# High_Side_FETs.net
KiCad netlist of a schematic drawn in Altium Designer
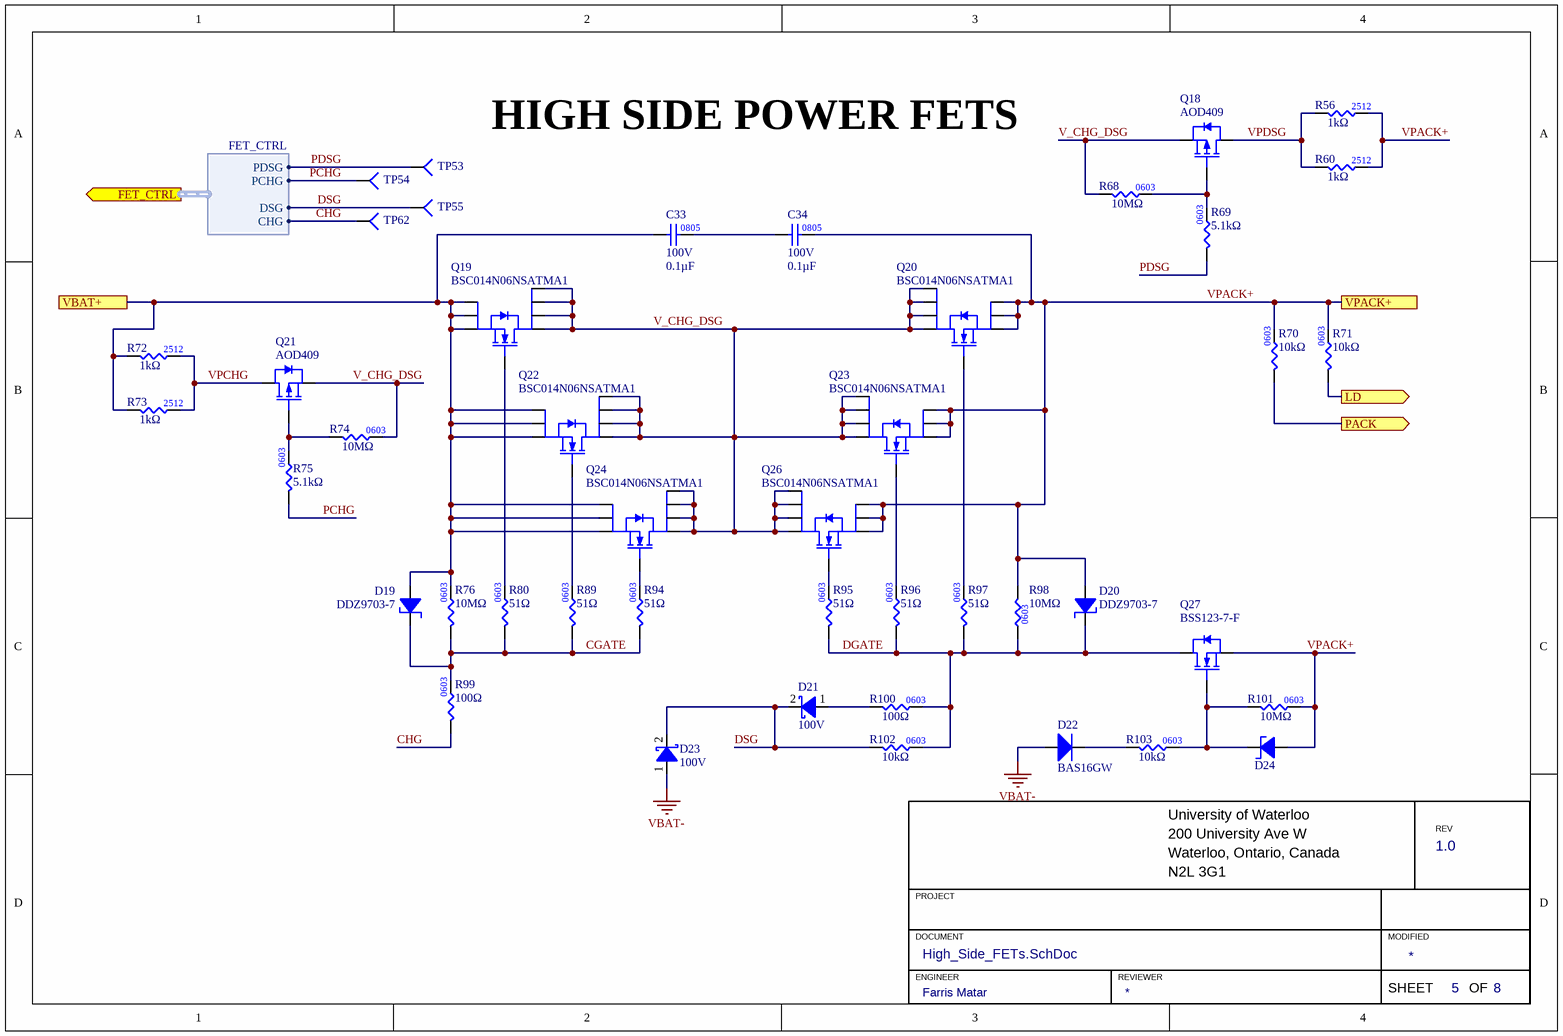
[diagram p0: High_Side_FETs.SchDoc]

(export (version "E")
  (design (tool "Eeschema 10.0.6"))
  (components
    (comp (ref "C33")
      (value "0.1µF")
      (footprint "CAP0805")
      (description "CAP CER 0.1UF 100V X7R 0805")
      (fields (field (name "VOLTAGE RATING") "100V") (field (name "Comment") "CAP_0.1uF_100V_0805"))
      (libsource (lib "Personal_Schematic_Library_2022") (part "CAP_0.1uF_100V_0805"))
    )
    (comp (ref "C34")
      (value "0.1µF")
      (footprint "CAP0805")
      (description "CAP CER 0.1UF 100V X7R 0805")
      (fields (field (name "VOLTAGE RATING") "100V") (field (name "Comment") "CAP_0.1uF_100V_0805"))
      (libsource (lib "Personal_Schematic_Library_2022") (part "CAP_0.1uF_100V_0805"))
    )
    (comp (ref "D19")
      (value "DIO_ZENER_16V")
      (footprint "SOD-123_FLAT")
      (description "DIODE ZENER 16V 500MW SOD123")
      (fields (field (name "MANUFACTURER PART NUMBER 1") "DDZ9703-7"))
      (libsource (lib "Personal_Schematic_Library_2022") (part "DIO_ZENER_16V"))
    )
    (comp (ref "D20")
      (value "DIO_ZENER_16V")
      (footprint "SOD-123_FLAT")
      (description "DIODE ZENER 16V 500MW SOD123")
      (fields (field (name "MANUFACTURER PART NUMBER 1") "DDZ9703-7"))
      (libsource (lib "Personal_Schematic_Library_2022") (part "DIO_ZENER_16V"))
    )
    (comp (ref "D21")
      (value "DIO_SCHOTTKY_100V_1A")
      (footprint "SOD-123_FLAT")
      (description "DIODE SCHOTTKY 100V 1A SOD-123F")
      (fields (field (name "VR (MAX)") "100V"))
      (libsource (lib "Personal_Schematic_Library_2022") (part "DIO_SCHOTTKY_100V_1A"))
    )
    (comp (ref "D22")
      (value "DIO_100V_215mA")
      (footprint "DIODSOD-123")
      (description "DIODE GEN PURP 100V 215MA SOD123")
      (fields (field (name "MANUFACTURER PART NUMBER 1") "BAS16GW"))
      (libsource (lib "Personal_Schematic_Library_2022") (part "DIO_100V_215mA"))
    )
    (comp (ref "D23")
      (value "DIO_SCHOTTKY_100V_1A")
      (footprint "SOD-123_FLAT")
      (description "DIODE SCHOTTKY 100V 1A SOD-123F")
      (fields (field (name "VR (MAX)") "100V"))
      (libsource (lib "Personal_Schematic_Library_2022") (part "DIO_SCHOTTKY_100V_1A"))
    )
    (comp (ref "D24")
      (value "DIO_ZENER_16V")
      (footprint "SOD-123_FLAT")
      (description "DIODE ZENER 16V 500MW SOD123")
      (libsource (lib "Personal_Schematic_Library_2022") (part "DIO_ZENER_16V"))
    )
    (comp (ref "Q18")
      (value "PMOS_60V_26A")
      (footprint "TO-252 AOSMD")
      (description "MOSFET P-CH 60V 26A TO252")
      (fields (field (name "MANUFACTURER PART NUMBER 1") "AOD409"))
      (libsource (lib "Personal_Schematic_Library_2022") (part "PMOS_60V_26A"))
    )
    (comp (ref "Q19")
      (value "NMOS_60V_30A")
      (footprint "INFINEON_8-POWERTDFN")
      (description "MOSFET N-CH 60V 30A/100A TDSON7")
      (fields (field (name "MANUFACTURER PART NUMBER 1") "BSC014N06NSATMA1"))
      (libsource (lib "Personal_Schematic_Library_2022") (part "NMOS_60V_30A"))
    )
    (comp (ref "Q20")
      (value "NMOS_60V_30A")
      (footprint "INFINEON_8-POWERTDFN")
      (description "MOSFET N-CH 60V 30A/100A TDSON7")
      (fields (field (name "MANUFACTURER PART NUMBER 1") "BSC014N06NSATMA1"))
      (libsource (lib "Personal_Schematic_Library_2022") (part "NMOS_60V_30A"))
    )
    (comp (ref "Q21")
      (value "PMOS_60V_26A")
      (footprint "TO-252 AOSMD")
      (description "MOSFET P-CH 60V 26A TO252")
      (fields (field (name "MANUFACTURER PART NUMBER 1") "AOD409"))
      (libsource (lib "Personal_Schematic_Library_2022") (part "PMOS_60V_26A"))
    )
    (comp (ref "Q22")
      (value "NMOS_60V_30A")
      (footprint "INFINEON_8-POWERTDFN")
      (description "MOSFET N-CH 60V 30A/100A TDSON7")
      (fields (field (name "MANUFACTURER PART NUMBER 1") "BSC014N06NSATMA1"))
      (libsource (lib "Personal_Schematic_Library_2022") (part "NMOS_60V_30A"))
    )
    (comp (ref "Q23")
      (value "NMOS_60V_30A")
      (footprint "INFINEON_8-POWERTDFN")
      (description "MOSFET N-CH 60V 30A/100A TDSON7")
      (fields (field (name "MANUFACTURER PART NUMBER 1") "BSC014N06NSATMA1"))
      (libsource (lib "Personal_Schematic_Library_2022") (part "NMOS_60V_30A"))
    )
    (comp (ref "Q24")
      (value "NMOS_60V_30A")
      (footprint "INFINEON_8-POWERTDFN")
      (description "MOSFET N-CH 60V 30A/100A TDSON7")
      (fields (field (name "MANUFACTURER PART NUMBER 1") "BSC014N06NSATMA1"))
      (libsource (lib "Personal_Schematic_Library_2022") (part "NMOS_60V_30A"))
    )
    (comp (ref "Q26")
      (value "NMOS_60V_30A")
      (footprint "INFINEON_8-POWERTDFN")
      (description "MOSFET N-CH 60V 30A/100A TDSON7")
      (fields (field (name "MANUFACTURER PART NUMBER 1") "BSC014N06NSATMA1"))
      (libsource (lib "Personal_Schematic_Library_2022") (part "NMOS_60V_30A"))
    )
    (comp (ref "Q27")
      (value "NMOS_100V_170mA")
      (footprint "SOT23-3")
      (description "MOSFET N-CH 100V 170MA SOT23-3")
      (fields (field (name "MANUFACTURER PART NUMBER 1") "BSS123-7-F"))
      (libsource (lib "Personal_Schematic_Library_2022") (part "NMOS_100V_170mA"))
    )
    (comp (ref "R56")
      (value "1kΩ")
      (footprint "RES2512")
      (description "RES SMD 1K OHM 1% 3W 2512")
      (fields (field (name "Comment") "RES_1kΩ_2512_1%"))
      (libsource (lib "Personal_Schematic_Library_2022") (part "RES_1kΩ_2512_1%"))
    )
    (comp (ref "R60")
      (value "1kΩ")
      (footprint "RES2512")
      (description "RES SMD 1K OHM 1% 3W 2512")
      (fields (field (name "Comment") "RES_1kΩ_2512_1%"))
      (libsource (lib "Personal_Schematic_Library_2022") (part "RES_1kΩ_2512_1%"))
    )
    (comp (ref "R68")
      (value "10MΩ")
      (footprint "RES0603")
      (description "RES 10M OHM 1% 1/10W 0603")
      (fields (field (name "Comment") "RES_10MΩ_0603_1%"))
      (libsource (lib "Personal_Schematic_Library_2022") (part "RES_10MΩ_0603_1%"))
    )
    (comp (ref "R69")
      (value "5.1kΩ")
      (footprint "RES0603")
      (description "RES 5.1K OHM 1% 1/10W 0603")
      (fields (field (name "Comment") "RES_5.1kΩ_0603_1%"))
      (libsource (lib "Personal_Schematic_Library_2022") (part "RES_5.1kΩ_0603_1%"))
    )
    (comp (ref "R70")
      (value "10kΩ")
      (footprint "RES0603")
      (description "RES 10K OHM 1% 1/8W 0603")
      (fields (field (name "Comment") "RES_10kΩ_0603_1%"))
      (libsource (lib "Personal_Schematic_Library_2022") (part "RES_10kΩ_0603_1%"))
    )
    (comp (ref "R71")
      (value "10kΩ")
      (footprint "RES0603")
      (description "RES 10K OHM 1% 1/8W 0603")
      (fields (field (name "Comment") "RES_10kΩ_0603_1%"))
      (libsource (lib "Personal_Schematic_Library_2022") (part "RES_10kΩ_0603_1%"))
    )
    (comp (ref "R72")
      (value "1kΩ")
      (footprint "RES2512")
      (description "RES SMD 1K OHM 1% 3W 2512")
      (fields (field (name "Comment") "RES_1kΩ_2512_1%"))
      (libsource (lib "Personal_Schematic_Library_2022") (part "RES_1kΩ_2512_1%"))
    )
    (comp (ref "R73")
      (value "1kΩ")
      (footprint "RES2512")
      (description "RES SMD 1K OHM 1% 3W 2512")
      (fields (field (name "Comment") "RES_1kΩ_2512_1%"))
      (libsource (lib "Personal_Schematic_Library_2022") (part "RES_1kΩ_2512_1%"))
    )
    (comp (ref "R74")
      (value "10MΩ")
      (footprint "RES0603")
      (description "RES 10M OHM 1% 1/10W 0603")
      (fields (field (name "Comment") "RES_10MΩ_0603_1%"))
      (libsource (lib "Personal_Schematic_Library_2022") (part "RES_10MΩ_0603_1%"))
    )
    (comp (ref "R75")
      (value "5.1kΩ")
      (footprint "RES0603")
      (description "RES 5.1K OHM 1% 1/10W 0603")
      (fields (field (name "Comment") "RES_5.1kΩ_0603_1%"))
      (libsource (lib "Personal_Schematic_Library_2022") (part "RES_5.1kΩ_0603_1%"))
    )
    (comp (ref "R76")
      (value "10MΩ")
      (footprint "RES0603")
      (description "RES 10M OHM 1% 1/10W 0603")
      (fields (field (name "Comment") "RES_10MΩ_0603_1%"))
      (libsource (lib "Personal_Schematic_Library_2022") (part "RES_10MΩ_0603_1%"))
    )
    (comp (ref "R80")
      (value "51Ω")
      (footprint "RES0603")
      (description "RES 51 OHM 1% 1/10W 0603")
      (fields (field (name "Comment") "RES_51Ω_0603_1%"))
      (libsource (lib "Personal_Schematic_Library_2022") (part "RES_51Ω_0603_1%"))
    )
    (comp (ref "R89")
      (value "51Ω")
      (footprint "RES0603")
      (description "RES 51 OHM 1% 1/10W 0603")
      (fields (field (name "Comment") "RES_51Ω_0603_1%"))
      (libsource (lib "Personal_Schematic_Library_2022") (part "RES_51Ω_0603_1%"))
    )
    (comp (ref "R94")
      (value "51Ω")
      (footprint "RES0603")
      (description "RES 51 OHM 1% 1/10W 0603")
      (fields (field (name "Comment") "RES_51Ω_0603_1%"))
      (libsource (lib "Personal_Schematic_Library_2022") (part "RES_51Ω_0603_1%"))
    )
    (comp (ref "R95")
      (value "51Ω")
      (footprint "RES0603")
      (description "RES 51 OHM 1% 1/10W 0603")
      (fields (field (name "Comment") "RES_51Ω_0603_1%"))
      (libsource (lib "Personal_Schematic_Library_2022") (part "RES_51Ω_0603_1%"))
    )
    (comp (ref "R96")
      (value "51Ω")
      (footprint "RES0603")
      (description "RES 51 OHM 1% 1/10W 0603")
      (fields (field (name "Comment") "RES_51Ω_0603_1%"))
      (libsource (lib "Personal_Schematic_Library_2022") (part "RES_51Ω_0603_1%"))
    )
    (comp (ref "R97")
      (value "51Ω")
      (footprint "RES0603")
      (description "RES 51 OHM 1% 1/10W 0603")
      (fields (field (name "Comment") "RES_51Ω_0603_1%"))
      (libsource (lib "Personal_Schematic_Library_2022") (part "RES_51Ω_0603_1%"))
    )
    (comp (ref "R98")
      (value "10MΩ")
      (footprint "RES0603")
      (description "RES 10M OHM 1% 1/10W 0603")
      (fields (field (name "Comment") "RES_10MΩ_0603_1%"))
      (libsource (lib "Personal_Schematic_Library_2022") (part "RES_10MΩ_0603_1%"))
    )
    (comp (ref "R99")
      (value "100Ω")
      (footprint "RES0603")
      (description "RES 100 OHM 1% 1/10W 0603")
      (fields (field (name "Comment") "RES_100Ω_0603_1%"))
      (libsource (lib "Personal_Schematic_Library_2022") (part "RES_100Ω_0603_1%"))
    )
    (comp (ref "R100")
      (value "100Ω")
      (footprint "RES0603")
      (description "RES 100 OHM 1% 1/10W 0603")
      (fields (field (name "Comment") "RES_100Ω_0603_1%"))
      (libsource (lib "Personal_Schematic_Library_2022") (part "RES_100Ω_0603_1%"))
    )
    (comp (ref "R101")
      (value "10MΩ")
      (footprint "RES0603")
      (description "RES 10M OHM 1% 1/10W 0603")
      (fields (field (name "Comment") "RES_10MΩ_0603_1%"))
      (libsource (lib "Personal_Schematic_Library_2022") (part "RES_10MΩ_0603_1%"))
    )
    (comp (ref "R102")
      (value "10kΩ")
      (footprint "RES0603")
      (description "RES 10K OHM 1% 1/8W 0603")
      (fields (field (name "Comment") "RES_10kΩ_0603_1%"))
      (libsource (lib "Personal_Schematic_Library_2022") (part "RES_10kΩ_0603_1%"))
    )
    (comp (ref "R103")
      (value "10kΩ")
      (footprint "RES0603")
      (description "RES 10K OHM 1% 1/8W 0603")
      (fields (field (name "Comment") "RES_10kΩ_0603_1%"))
      (libsource (lib "Personal_Schematic_Library_2022") (part "RES_10kΩ_0603_1%"))
    )
    (comp (ref "TP53")
      (value "TESTPOINT_1MM_CIRCLE")
      (footprint "TESTPOINT_CIRCLE_1MM")
      (description "TESTPOINT 1MM CIRCLE")
      (libsource (lib "Personal_Schematic_Library_2022") (part "TESTPOINT_1MM_CIRCLE"))
    )
    (comp (ref "TP54")
      (value "TESTPOINT_1MM_CIRCLE")
      (footprint "TESTPOINT_CIRCLE_1MM")
      (description "TESTPOINT 1MM CIRCLE")
      (libsource (lib "Personal_Schematic_Library_2022") (part "TESTPOINT_1MM_CIRCLE"))
    )
    (comp (ref "TP55")
      (value "TESTPOINT_1MM_CIRCLE")
      (footprint "TESTPOINT_CIRCLE_1MM")
      (description "TESTPOINT 1MM CIRCLE")
      (libsource (lib "Personal_Schematic_Library_2022") (part "TESTPOINT_1MM_CIRCLE"))
    )
    (comp (ref "TP62")
      (value "TESTPOINT_1MM_CIRCLE")
      (footprint "TESTPOINT_CIRCLE_1MM")
      (description "TESTPOINT 1MM CIRCLE")
      (libsource (lib "Personal_Schematic_Library_2022") (part "TESTPOINT_1MM_CIRCLE"))
    )
  )
  (nets
    (net (code "2") (name "/CGATE") (class "Default")
      (node (ref "D19") (pin "2") (pinfunction "Cathode_2") (pintype "passive"))
      (node (ref "R76") (pin "1") (pinfunction "1_1") (pintype "passive"))
      (node (ref "R80") (pin "1") (pinfunction "1_1") (pintype "passive"))
      (node (ref "R89") (pin "1") (pinfunction "1_1") (pintype "passive"))
      (node (ref "R94") (pin "1") (pinfunction "1_1") (pintype "passive"))
      (node (ref "R99") (pin "2") (pinfunction "2_2") (pintype "passive"))
    )
    (net (code "3") (name "/CHG") (class "Default")
      (node (ref "R99") (pin "1") (pinfunction "1_1") (pintype "passive"))
      (node (ref "TP62") (pin "1") (pinfunction "=value_1") (pintype "passive"))
    )
    (net (code "4") (name "/DGATE") (class "Default")
      (node (ref "D20") (pin "2") (pinfunction "Cathode_2") (pintype "passive"))
      (node (ref "Q27") (pin "3") (pinfunction "DRAIN_3") (pintype "passive"))
      (node (ref "R100") (pin "2") (pinfunction "2_2") (pintype "passive"))
      (node (ref "R102") (pin "2") (pinfunction "2_2") (pintype "passive"))
      (node (ref "R95") (pin "1") (pinfunction "1_1") (pintype "passive"))
      (node (ref "R96") (pin "1") (pinfunction "1_1") (pintype "passive"))
      (node (ref "R97") (pin "1") (pinfunction "1_1") (pintype "passive"))
      (node (ref "R98") (pin "1") (pinfunction "1_1") (pintype "passive"))
    )
    (net (code "5") (name "/DSG") (class "Default")
      (node (ref "D21") (pin "2") (pinfunction "Cathode_2") (pintype "passive"))
      (node (ref "D23") (pin "2") (pinfunction "Cathode_2") (pintype "passive"))
      (node (ref "R102") (pin "1") (pinfunction "1_1") (pintype "passive"))
      (node (ref "TP55") (pin "1") (pinfunction "=value_1") (pintype "passive"))
    )
    (net (code "6") (name "/LD") (class "Default")
      (node (ref "R71") (pin "1") (pinfunction "1_1") (pintype "passive"))
    )
    (net (code "7") (name "/PACK") (class "Default")
      (node (ref "R70") (pin "1") (pinfunction "1_1") (pintype "passive"))
    )
    (net (code "8") (name "/PCHG") (class "Default")
      (node (ref "R75") (pin "1") (pinfunction "1_1") (pintype "passive"))
      (node (ref "TP54") (pin "1") (pinfunction "=value_1") (pintype "passive"))
    )
    (net (code "9") (name "/PDSG") (class "Default")
      (node (ref "R69") (pin "1") (pinfunction "1_1") (pintype "passive"))
      (node (ref "TP53") (pin "1") (pinfunction "=value_1") (pintype "passive"))
    )
    (net (code "10") (name "/VBAT+") (class "Default")
      (node (ref "C33") (pin "1") (pinfunction "1_1") (pintype "passive"))
      (node (ref "D19") (pin "1") (pinfunction "Anode_1") (pintype "passive"))
      (node (ref "Q19") (pin "1") (pinfunction "Source_1") (pintype "passive"))
      (node (ref "Q19") (pin "2") (pinfunction "Source_2") (pintype "passive"))
      (node (ref "Q19") (pin "3") (pinfunction "Source_3") (pintype "passive"))
      (node (ref "Q22") (pin "1") (pinfunction "Source_1") (pintype "passive"))
      (node (ref "Q22") (pin "2") (pinfunction "Source_2") (pintype "passive"))
      (node (ref "Q22") (pin "3") (pinfunction "Source_3") (pintype "passive"))
      (node (ref "Q24") (pin "1") (pinfunction "Source_1") (pintype "passive"))
      (node (ref "Q24") (pin "2") (pinfunction "Source_2") (pintype "passive"))
      (node (ref "Q24") (pin "3") (pinfunction "Source_3") (pintype "passive"))
      (node (ref "R72") (pin "1") (pinfunction "1_1") (pintype "passive"))
      (node (ref "R73") (pin "1") (pinfunction "1_1") (pintype "passive"))
      (node (ref "R76") (pin "2") (pinfunction "2_2") (pintype "passive"))
    )
    (net (code "11") (name "/VPACK+") (class "Default")
      (node (ref "C34") (pin "2") (pinfunction "2_2") (pintype "passive"))
      (node (ref "D20") (pin "1") (pinfunction "Anode_1") (pintype "passive"))
      (node (ref "D24") (pin "1") (pinfunction "Anode_1") (pintype "passive"))
      (node (ref "Q20") (pin "1") (pinfunction "Source_1") (pintype "passive"))
      (node (ref "Q20") (pin "2") (pinfunction "Source_2") (pintype "passive"))
      (node (ref "Q20") (pin "3") (pinfunction "Source_3") (pintype "passive"))
      (node (ref "Q23") (pin "1") (pinfunction "Source_1") (pintype "passive"))
      (node (ref "Q23") (pin "2") (pinfunction "Source_2") (pintype "passive"))
      (node (ref "Q23") (pin "3") (pinfunction "Source_3") (pintype "passive"))
      (node (ref "Q26") (pin "1") (pinfunction "Source_1") (pintype "passive"))
      (node (ref "Q26") (pin "2") (pinfunction "Source_2") (pintype "passive"))
      (node (ref "Q26") (pin "3") (pinfunction "Source_3") (pintype "passive"))
      (node (ref "Q27") (pin "2") (pinfunction "SOURCE_2") (pintype "passive"))
      (node (ref "R101") (pin "2") (pinfunction "2_2") (pintype "passive"))
      (node (ref "R56") (pin "2") (pinfunction "2_2") (pintype "passive"))
      (node (ref "R60") (pin "2") (pinfunction "2_2") (pintype "passive"))
      (node (ref "R70") (pin "2") (pinfunction "2_2") (pintype "passive"))
      (node (ref "R71") (pin "2") (pinfunction "2_2") (pintype "passive"))
      (node (ref "R98") (pin "2") (pinfunction "2_2") (pintype "passive"))
    )
    (net (code "12") (name "/VPCHG") (class "Default")
      (node (ref "Q21") (pin "2") (pinfunction "Drain_2") (pintype "passive"))
      (node (ref "R72") (pin "2") (pinfunction "2_2") (pintype "passive"))
      (node (ref "R73") (pin "2") (pinfunction "2_2") (pintype "passive"))
    )
    (net (code "13") (name "/VPDSG") (class "Default")
      (node (ref "Q18") (pin "2") (pinfunction "Drain_2") (pintype "passive"))
      (node (ref "R56") (pin "1") (pinfunction "1_1") (pintype "passive"))
      (node (ref "R60") (pin "1") (pinfunction "1_1") (pintype "passive"))
    )
    (net (code "14") (name "/V_CHG_DSG") (class "Default")
      (node (ref "Q18") (pin "3") (pinfunction "Source_3") (pintype "passive"))
      (node (ref "Q19") (pin "5") (pinfunction "Drain_5") (pintype "passive"))
      (node (ref "Q19") (pin "6") (pinfunction "Drain_6") (pintype "passive"))
      (node (ref "Q19") (pin "7") (pinfunction "Drain_7") (pintype "passive"))
      (node (ref "Q19") (pin "8") (pinfunction "Drain_8") (pintype "passive"))
      (node (ref "Q20") (pin "5") (pinfunction "Drain_5") (pintype "passive"))
      (node (ref "Q20") (pin "6") (pinfunction "Drain_6") (pintype "passive"))
      (node (ref "Q20") (pin "7") (pinfunction "Drain_7") (pintype "passive"))
      (node (ref "Q20") (pin "8") (pinfunction "Drain_8") (pintype "passive"))
      (node (ref "Q21") (pin "3") (pinfunction "Source_3") (pintype "passive"))
      (node (ref "Q22") (pin "5") (pinfunction "Drain_5") (pintype "passive"))
      (node (ref "Q22") (pin "6") (pinfunction "Drain_6") (pintype "passive"))
      (node (ref "Q22") (pin "7") (pinfunction "Drain_7") (pintype "passive"))
      (node (ref "Q22") (pin "8") (pinfunction "Drain_8") (pintype "passive"))
      (node (ref "Q23") (pin "5") (pinfunction "Drain_5") (pintype "passive"))
      (node (ref "Q23") (pin "6") (pinfunction "Drain_6") (pintype "passive"))
      (node (ref "Q23") (pin "7") (pinfunction "Drain_7") (pintype "passive"))
      (node (ref "Q23") (pin "8") (pinfunction "Drain_8") (pintype "passive"))
      (node (ref "Q24") (pin "5") (pinfunction "Drain_5") (pintype "passive"))
      (node (ref "Q24") (pin "6") (pinfunction "Drain_6") (pintype "passive"))
      (node (ref "Q24") (pin "7") (pinfunction "Drain_7") (pintype "passive"))
      (node (ref "Q24") (pin "8") (pinfunction "Drain_8") (pintype "passive"))
      (node (ref "Q26") (pin "5") (pinfunction "Drain_5") (pintype "passive"))
      (node (ref "Q26") (pin "6") (pinfunction "Drain_6") (pintype "passive"))
      (node (ref "Q26") (pin "7") (pinfunction "Drain_7") (pintype "passive"))
      (node (ref "Q26") (pin "8") (pinfunction "Drain_8") (pintype "passive"))
      (node (ref "R68") (pin "1") (pinfunction "1_1") (pintype "passive"))
      (node (ref "R74") (pin "2") (pinfunction "2_2") (pintype "passive"))
    )
    (net (code "16") (name "Net-(C33-Pad2)") (class "Default")
      (node (ref "C33") (pin "2") (pinfunction "2_2") (pintype "passive"))
      (node (ref "C34") (pin "1") (pinfunction "1_1") (pintype "passive"))
    )
    (net (code "17") (name "Net-(D21-Anode)") (class "Default")
      (node (ref "D21") (pin "1") (pinfunction "Anode_1") (pintype "passive"))
      (node (ref "R100") (pin "1") (pinfunction "1_1") (pintype "passive"))
    )
    (net (code "18") (name "Net-(D22-K)") (class "Default")
      (node (ref "D22") (pin "2") (pinfunction "K_2") (pintype "passive"))
      (node (ref "R103") (pin "1") (pinfunction "1_1") (pintype "passive"))
    )
    (net (code "19") (name "Net-(D24-Cathode)") (class "Default")
      (node (ref "D24") (pin "2") (pinfunction "Cathode_2") (pintype "passive"))
      (node (ref "Q27") (pin "1") (pinfunction "GATE_1") (pintype "passive"))
      (node (ref "R101") (pin "1") (pinfunction "1_1") (pintype "passive"))
      (node (ref "R103") (pin "2") (pinfunction "2_2") (pintype "passive"))
    )
    (net (code "20") (name "Net-(Q18-Gate)") (class "Default")
      (node (ref "Q18") (pin "1") (pinfunction "Gate_1") (pintype "passive"))
      (node (ref "R68") (pin "2") (pinfunction "2_2") (pintype "passive"))
      (node (ref "R69") (pin "2") (pinfunction "2_2") (pintype "passive"))
    )
    (net (code "21") (name "Net-(Q19-Gate)") (class "Default")
      (node (ref "Q19") (pin "4") (pinfunction "Gate_4") (pintype "passive"))
      (node (ref "R80") (pin "2") (pinfunction "2_2") (pintype "passive"))
    )
    (net (code "22") (name "Net-(Q20-Gate)") (class "Default")
      (node (ref "Q20") (pin "4") (pinfunction "Gate_4") (pintype "passive"))
      (node (ref "R97") (pin "2") (pinfunction "2_2") (pintype "passive"))
    )
    (net (code "23") (name "Net-(Q21-Gate)") (class "Default")
      (node (ref "Q21") (pin "1") (pinfunction "Gate_1") (pintype "passive"))
      (node (ref "R74") (pin "1") (pinfunction "1_1") (pintype "passive"))
      (node (ref "R75") (pin "2") (pinfunction "2_2") (pintype "passive"))
    )
    (net (code "24") (name "Net-(Q22-Gate)") (class "Default")
      (node (ref "Q22") (pin "4") (pinfunction "Gate_4") (pintype "passive"))
      (node (ref "R89") (pin "2") (pinfunction "2_2") (pintype "passive"))
    )
    (net (code "25") (name "Net-(Q23-Gate)") (class "Default")
      (node (ref "Q23") (pin "4") (pinfunction "Gate_4") (pintype "passive"))
      (node (ref "R96") (pin "2") (pinfunction "2_2") (pintype "passive"))
    )
    (net (code "26") (name "Net-(Q24-Gate)") (class "Default")
      (node (ref "Q24") (pin "4") (pinfunction "Gate_4") (pintype "passive"))
      (node (ref "R94") (pin "2") (pinfunction "2_2") (pintype "passive"))
    )
    (net (code "27") (name "Net-(Q26-Gate)") (class "Default")
      (node (ref "Q26") (pin "4") (pinfunction "Gate_4") (pintype "passive"))
      (node (ref "R95") (pin "2") (pinfunction "2_2") (pintype "passive"))
    )
    (net (code "28") (name "VBAT-") (class "Default")
      (node (ref "D22") (pin "1") (pinfunction "A_1") (pintype "passive"))
      (node (ref "D23") (pin "1") (pinfunction "Anode_1") (pintype "passive"))
    )
  )
)
